# STeaMi-FP4-Alimentation.net
KiCad netlist of a schematic drawn in Altium Designer
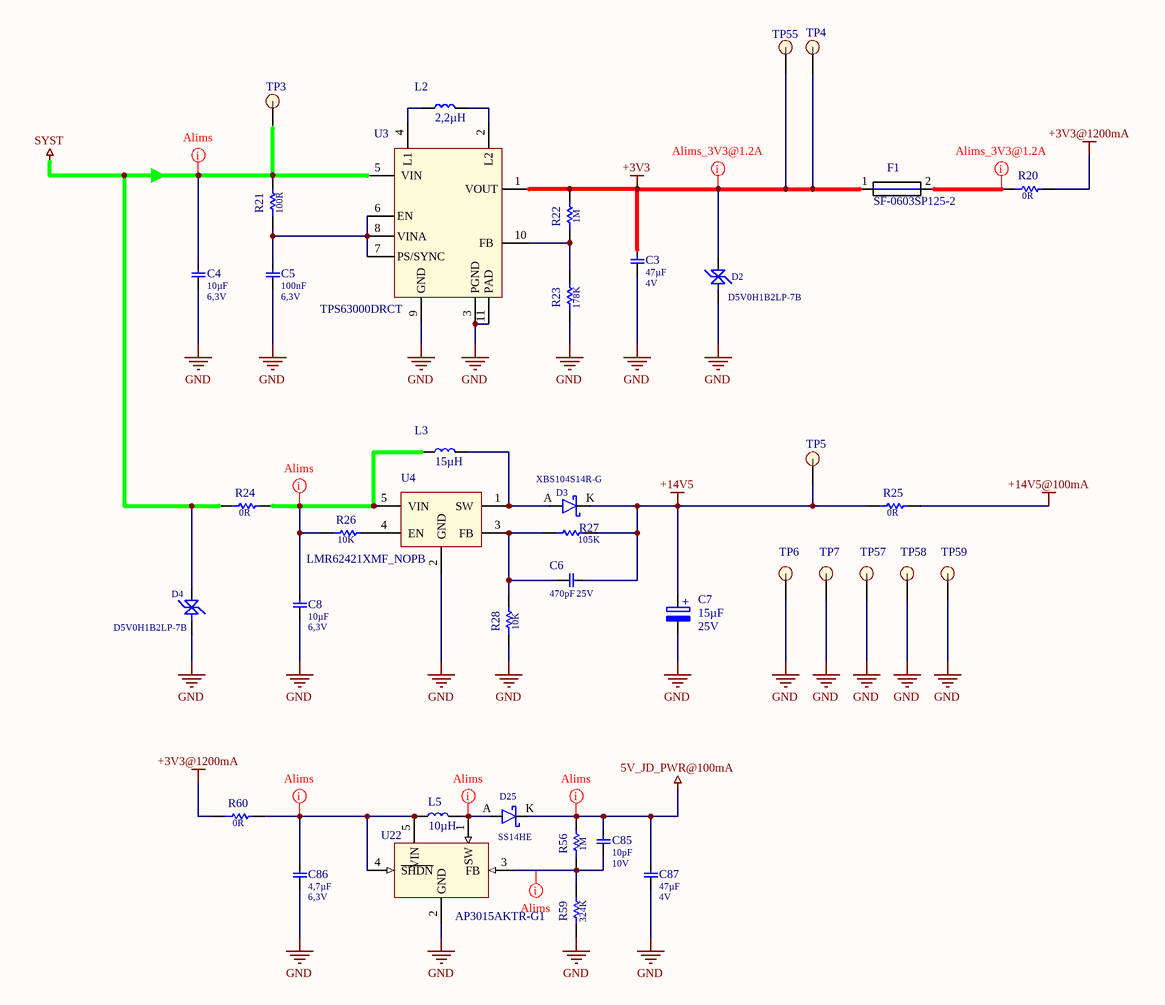
[diagram p0: STeaMi-FP4-Alimentation.SchDoc]

(export (version "E")
  (design (tool "Eeschema 10.0.6"))
  (components
    (comp (ref "C3")
      (value "~")
      (footprint "0603-CAP")
      (description "CAP CER 47µF 4V X5R 0603")
      (fields
        (field (name "MANUFACTURER") "Taiyo Yuden")
        (field (name "MANUFACTURER PART NUMBER") "AMK107BBJ476MA-RE")
        (field (name "CAPACITANCE") "47µF")
        (field (name "VOLTAGE") "4V")
        (field (name "CREATED BY") "EAG")
        (field (name "CHECKED BY") "*")
      )
      (libsource (lib "ComponentDB") (part "CAP_SYMBOL"))
    )
    (comp (ref "C4")
      (value "~")
      (footprint "0402-CAP")
      (description "CAP CER 10µF 6,3V X5R 0402")
      (fields
        (field (name "MANUFACTURER") "Murata")
        (field (name "MANUFACTURER PART NUMBER") "GRM155R60J106ME15D")
        (field (name "CAPACITANCE") "10µF")
        (field (name "VOLTAGE") "6,3V")
        (field (name "CREATED BY") "EAG")
        (field (name "CHECKED BY") "*")
      )
      (libsource (lib "ComponentDB") (part "CAP_SYMBOL"))
    )
    (comp (ref "C5")
      (value "~")
      (footprint "0402-CAP")
      (description "CAP CER 100nF 6,3V X5R 0402")
      (fields
        (field (name "MANUFACTURER") "Kyocera AVX")
        (field (name "MANUFACTURER PART NUMBER") "0402YD104KAT2A")
        (field (name "CAPACITANCE") "100nF")
        (field (name "VOLTAGE") "6,3V")
        (field (name "CREATED BY") "EAG")
        (field (name "CHECKED BY") "*")
      )
      (libsource (lib "ComponentDB") (part "CAP_SYMBOL"))
    )
    (comp (ref "C6")
      (value "~")
      (footprint "0402-CAP")
      (description "CAP CER 470pF 25V X7R 0402")
      (fields
        (field (name "MANUFACTURER") "Yageo")
        (field (name "MANUFACTURER PART NUMBER") "AC0402KRX7R8BB471")
        (field (name "CAPACITANCE") "470pF")
        (field (name "VOLTAGE") "25V")
        (field (name "CREATED BY") "EAG")
        (field (name "CHECKED BY") "*")
      )
      (libsource (lib "ComponentDB") (part "CAP_SYMBOL"))
    )
    (comp (ref "C7")
      (value "~")
      (footprint "CAPC3225X55N_1210 - TANTAL")
      (description "CAP CER 15µF 25V TANT 1210")
      (fields
        (field (name "MANUFACTURER") "Panasonic")
        (field (name "MANUFACTURER PART NUMBER") "25TQC15MYFB")
        (field (name "CAPACITANCE") "15µF")
        (field (name "VOLTAGE") "25V")
        (field (name "CREATED BY") "EAG")
      )
      (libsource (lib "ComponentDB") (part "CAP_POL_SYMBOL"))
    )
    (comp (ref "C8")
      (value "~")
      (footprint "0402-CAP")
      (description "CAP CER 10µF 6,3V X5R 0402")
      (fields
        (field (name "MANUFACTURER") "Murata")
        (field (name "MANUFACTURER PART NUMBER") "GRM155R60J106ME15D")
        (field (name "CAPACITANCE") "10µF")
        (field (name "VOLTAGE") "6,3V")
        (field (name "CREATED BY") "EAG")
        (field (name "CHECKED BY") "*")
      )
      (libsource (lib "ComponentDB") (part "CAP_SYMBOL"))
    )
    (comp (ref "C85")
      (value "~")
      (footprint "0402-CAP")
      (description "CAP CER 10pF 10V COG 0402 5%")
      (fields
        (field (name "MANUFACTURER") "WURTH Electronics")
        (field (name "MANUFACTURER PART NUMBER") "885012005007")
        (field (name "CAPACITANCE") "10pF")
        (field (name "VOLTAGE") "10V")
        (field (name "CREATED BY") "EAG")
        (field (name "CHECKED BY") "*")
      )
      (libsource (lib "ComponentDB") (part "CAP_SYMBOL"))
    )
    (comp (ref "C86")
      (value "~")
      (footprint "0402-CAP")
      (description "CAP CER 4,7µF 6,3V X5R 0402")
      (fields
        (field (name "CAPACITANCE") "4,7µF")
        (field (name "VOLTAGE") "6,3V")
        (field (name "PART NUMBER") "4,7µF-20%-6,3V-X5R-0402")
        (field (name "CREATED BY") "EAG")
        (field (name "CHECKED BY") "*")
      )
      (libsource (lib "ComponentDB") (part "CAP_SYMBOL"))
    )
    (comp (ref "C87")
      (value "~")
      (footprint "0603-CAP")
      (description "CAP CER 47µF 4V X5R 0603")
      (fields
        (field (name "CAPACITANCE") "47µF")
        (field (name "VOLTAGE") "4V")
        (field (name "PART NUMBER") "47µF-20%-4V-X5R-0603")
        (field (name "CREATED BY") "EAG")
        (field (name "CHECKED BY") "*")
      )
      (libsource (lib "ComponentDB") (part "CAP_SYMBOL"))
    )
    (comp (ref "D2")
      (value "~")
      (footprint "DFN100X60X45-2N")
      (description "ESD Suppressors / TVS Diodes Transient Voltage Suppressor PP")
      (fields
        (field (name "MANUFACTURER") "Diodes Incorporated")
        (field (name "MANUFACTURER PART NUMBER") "D5V0H1B2LP-7B")
        (field (name "PART NUMBER") "D5V0H1B2LP-7B")
        (field (name "CREATED BY") "EAG")
      )
      (libsource (lib "ComponentDB") (part "SUPPRESSORS_DIODE"))
    )
    (comp (ref "D3")
      (value "~")
      (footprint "SODFL3516X120N")
      (description "Diode Schottky 40 V 1A Montage en surface SOD-123")
      (fields
        (field (name "MANUFACTURER") "Torex Semiconductor")
        (field (name "MANUFACTURER PART NUMBER") "XBS104S14R-G")
        (field (name "PART NUMBER") "XBS104S14R-G")
        (field (name "CREATED BY") "EAG")
      )
      (libsource (lib "ComponentDB") (part "DIODE_SCHOTTKY"))
    )
    (comp (ref "D4")
      (value "~")
      (footprint "DFN100X60X45-2N")
      (description "ESD Suppressors / TVS Diodes Transient Voltage Suppressor PP")
      (fields
        (field (name "MANUFACTURER") "Diodes Incorporated")
        (field (name "MANUFACTURER PART NUMBER") "D5V0H1B2LP-7B")
        (field (name "PART NUMBER") "D5V0H1B2LP-7B")
        (field (name "CREATED BY") "EAG")
      )
      (libsource (lib "ComponentDB") (part "SUPPRESSORS_DIODE"))
    )
    (comp (ref "D25")
      (value "~")
      (footprint "SOD2314X75N-SOD323HE")
      (description "Diode Schottky 40 V 1A Montage en surface SDO-323HE")
      (fields
        (field (name "MANUFACTURER") "OnSemiconductor")
        (field (name "MANUFACTURER PART NUMBER") "SS14HE")
        (field (name "PART NUMBER") "SS14HE")
        (field (name "CREATED BY") "EAG")
      )
      (libsource (lib "ComponentDB") (part "DIODE_SCHOTTKY"))
    )
    (comp (ref "F1")
      (value "~")
      (footprint "FUSM16081X45")
      (description "Fusible 50V 1,25 A Slow blow")
      (fields
        (field (name "PART NUMBER") "SF-0603SP125-2")
        (field (name "CREATED BY") "*")
        (field (name "CHECKED BY") "*")
      )
      (libsource (lib "ComponentDB") (part "FUSE_SYMBOL"))
    )
    (comp (ref "L2")
      (value "~")
      (footprint "VLS3012")
      (description "Fixed Inductor 10µH ± 20% 1,4A 3x3x1,2mm")
      (fields
        (field (name "MANUFACTURER") "TDK")
        (field (name "MANUFACTURER PART NUMBER") "VLS3012CX-2R2M-1")
        (field (name "INDUCTANCE") "2,2µH")
        (field (name "CREATED BY") "EAG")
      )
      (libsource (lib "ComponentDB") (part "BOB_SYMBOL"))
    )
    (comp (ref "L3")
      (value "~")
      (footprint "WE-LQS_4025")
      (description "Fixed Inductor 10µH ± 20% 1,4A 5,8mm")
      (fields
        (field (name "MANUFACTURER") "Wurth")
        (field (name "MANUFACTURER PART NUMBER") "74404043150A")
        (field (name "INDUCTANCE") "15µH")
        (field (name "CREATED BY") "EAG")
      )
      (libsource (lib "ComponentDB") (part "BOB_SYMBOL"))
    )
    (comp (ref "L5")
      (value "~")
      (footprint "VLS3012")
      (description "Fixed Inductor 10µH ± 20% 1,12A 3x3x1,2mm")
      (fields
        (field (name "MANUFACTURER") "TDK")
        (field (name "MANUFACTURER PART NUMBER") "VLS3012CX-100M-1")
        (field (name "INDUCTANCE") "10µH")
        (field (name "CREATED BY") "EAG")
      )
      (libsource (lib "ComponentDB") (part "BOB_SYMBOL"))
    )
    (comp (ref "R20")
      (value "~")
      (footprint "RESC1005X40N_0402")
      (description "RES CMS 0R5%-0,0625W-0402")
      (fields
        (field (name "MANUFACTURER") "Yageo")
        (field (name "MANUFACTURER PART NUMBER") "RC0402JR-100RL")
        (field (name "RESISTANCE") "0R")
        (field (name "CREATED BY") "EAG")
      )
      (libsource (lib "ComponentDB") (part "RES_SYMBOL"))
    )
    (comp (ref "R21")
      (value "~")
      (footprint "RESC1005X40N_0402")
      (description "RES CMS 100R5%-0,0625W-0402 ±100ppm/°C")
      (fields
        (field (name "MANUFACTURER") "Yageo")
        (field (name "MANUFACTURER PART NUMBER") "RC0402JR-07100RL")
        (field (name "RESISTANCE") "100R")
        (field (name "CREATED BY") "EAG")
      )
      (libsource (lib "ComponentDB") (part "RES_SYMBOL"))
    )
    (comp (ref "R22")
      (value "~")
      (footprint "RESC1005X40N_0402")
      (description "RES CMS 1M1%-0,125W-0402 ±0ppm/°C")
      (fields
        (field (name "MANUFACTURER") "Yageo")
        (field (name "MANUFACTURER PART NUMBER") "RC0402FR-7W1ML")
        (field (name "RESISTANCE") "1M")
        (field (name "CREATED BY") "EAG")
      )
      (libsource (lib "ComponentDB") (part "RES_SYMBOL"))
    )
    (comp (ref "R23")
      (value "~")
      (footprint "RESC1005X40N_0402")
      (description "RES CMS 178K1%-0,1W-0402 ±25ppm/°C")
      (fields
        (field (name "MANUFACTURER") "Panasonic")
        (field (name "MANUFACTURER PART NUMBER") "ERJ-2RKF1783X")
        (field (name "RESISTANCE") "178K")
        (field (name "CREATED BY") "EAG")
      )
      (libsource (lib "ComponentDB") (part "RES_SYMBOL"))
    )
    (comp (ref "R24")
      (value "~")
      (footprint "RESC1005X40N_0402")
      (description "RES CMS 0R5%-0,0625W-0402")
      (fields
        (field (name "MANUFACTURER") "Yageo")
        (field (name "MANUFACTURER PART NUMBER") "RC0402JR-100RL")
        (field (name "RESISTANCE") "0R")
        (field (name "CREATED BY") "EAG")
      )
      (libsource (lib "ComponentDB") (part "RES_SYMBOL"))
    )
    (comp (ref "R25")
      (value "~")
      (footprint "RESC1005X40N_0402")
      (description "RES CMS 0R5%-0,0625W-0402")
      (fields
        (field (name "MANUFACTURER") "Yageo")
        (field (name "MANUFACTURER PART NUMBER") "RC0402JR-100RL")
        (field (name "RESISTANCE") "0R")
        (field (name "CREATED BY") "EAG")
      )
      (libsource (lib "ComponentDB") (part "RES_SYMBOL"))
    )
    (comp (ref "R26")
      (value "~")
      (footprint "RESC1005X40N_0402")
      (description "RES CMS 10K1%-0,0625W-0402 ±100ppm/°C")
      (fields
        (field (name "MANUFACTURER") "Yageo")
        (field (name "MANUFACTURER PART NUMBER") "AC0402FR-1310KL")
        (field (name "RESISTANCE") "10K")
        (field (name "CREATED BY") "EAG")
      )
      (libsource (lib "ComponentDB") (part "RES_SYMBOL"))
    )
    (comp (ref "R27")
      (value "~")
      (footprint "RESC1005X40N_0402")
      (description "RES CMS 105K0,5%-0,1W-0402 ±0ppm/°C")
      (fields
        (field (name "MANUFACTURER") "Panasonic")
        (field (name "MANUFACTURER PART NUMBER") "ERJ-2RKF1053X")
        (field (name "RESISTANCE") "105K")
        (field (name "CREATED BY") "EAG")
      )
      (libsource (lib "ComponentDB") (part "RES_SYMBOL"))
    )
    (comp (ref "R28")
      (value "~")
      (footprint "RESC1005X40N_0402")
      (description "RES CMS 10K1%-0,0625W-0402 ±100ppm/°C")
      (fields
        (field (name "MANUFACTURER") "Yageo")
        (field (name "MANUFACTURER PART NUMBER") "AC0402FR-1310KL")
        (field (name "RESISTANCE") "10K")
        (field (name "CREATED BY") "EAG")
      )
      (libsource (lib "ComponentDB") (part "RES_SYMBOL"))
    )
    (comp (ref "R56")
      (value "~")
      (footprint "RESC1005X40N_0402")
      (description "RES CMS 1M1%-0,125W-0402 ±0ppm/°C")
      (fields
        (field (name "MANUFACTURER") "Yageo")
        (field (name "MANUFACTURER PART NUMBER") "RC0402FR-7W1ML")
        (field (name "RESISTANCE") "1M")
        (field (name "CREATED BY") "EAG")
      )
      (libsource (lib "ComponentDB") (part "RES_SYMBOL"))
    )
    (comp (ref "R59")
      (value "~")
      (footprint "RESC1005X40N_0402")
      (description "RES CMS 324K1%-0,0625W-0402 ±100ppm/°C")
      (fields
        (field (name "MANUFACTURER") "Yageo")
        (field (name "MANUFACTURER PART NUMBER") "AC0402FR-07324KL")
        (field (name "RESISTANCE") "324K")
        (field (name "CREATED BY") "EAG")
      )
      (libsource (lib "ComponentDB") (part "RES_SYMBOL"))
    )
    (comp (ref "R60")
      (value "~")
      (footprint "RESC1005X40N_0402")
      (description "RES CMS 0R5%-0,0625W-0402")
      (fields
        (field (name "MANUFACTURER") "Yageo")
        (field (name "MANUFACTURER PART NUMBER") "RC0402JR-100RL")
        (field (name "RESISTANCE") "0R")
        (field (name "CREATED BY") "EAG")
      )
      (libsource (lib "ComponentDB") (part "RES_SYMBOL"))
    )
    (comp (ref "TP3")
      (value "PAD")
      (footprint "Testpoint 1mm")
      (description "TESTPOINTPAD")
      (fields
        (field (name "MANUFACTURER") "Smartembed")
        (field (name "MANUFACTURER PART NUMBER") "TESTPOINT")
        (field (name "CREATED BY") "EAG")
      )
      (libsource (lib "ComponentDB") (part "TESTPOINT"))
    )
    (comp (ref "TP4")
      (value "PAD")
      (footprint "Testpoint 1mm")
      (description "TESTPOINTPAD")
      (fields
        (field (name "MANUFACTURER") "Smartembed")
        (field (name "MANUFACTURER PART NUMBER") "TESTPOINT")
        (field (name "CREATED BY") "EAG")
      )
      (libsource (lib "ComponentDB") (part "TESTPOINT"))
    )
    (comp (ref "TP5")
      (value "PAD")
      (footprint "Testpoint 1mm")
      (description "TESTPOINTPAD")
      (fields
        (field (name "MANUFACTURER") "Smartembed")
        (field (name "MANUFACTURER PART NUMBER") "TESTPOINT")
        (field (name "CREATED BY") "EAG")
      )
      (libsource (lib "ComponentDB") (part "TESTPOINT"))
    )
    (comp (ref "TP6")
      (value "PAD")
      (footprint "Testpoint 1mm")
      (description "TESTPOINTPAD")
      (fields
        (field (name "MANUFACTURER") "Smartembed")
        (field (name "MANUFACTURER PART NUMBER") "TESTPOINT")
        (field (name "CREATED BY") "EAG")
      )
      (libsource (lib "ComponentDB") (part "TESTPOINT"))
    )
    (comp (ref "TP7")
      (value "PAD")
      (footprint "Testpoint 1mm")
      (description "TESTPOINTPAD")
      (fields
        (field (name "MANUFACTURER") "Smartembed")
        (field (name "MANUFACTURER PART NUMBER") "TESTPOINT")
        (field (name "CREATED BY") "EAG")
      )
      (libsource (lib "ComponentDB") (part "TESTPOINT"))
    )
    (comp (ref "TP55")
      (value "PAD")
      (footprint "Testpoint 1mm")
      (description "TESTPOINTPAD")
      (fields
        (field (name "MANUFACTURER") "Smartembed")
        (field (name "MANUFACTURER PART NUMBER") "TESTPOINT")
        (field (name "CREATED BY") "EAG")
      )
      (libsource (lib "ComponentDB") (part "TESTPOINT"))
    )
    (comp (ref "TP57")
      (value "PAD")
      (footprint "Testpoint 1mm")
      (description "TESTPOINTPAD")
      (fields
        (field (name "MANUFACTURER") "Smartembed")
        (field (name "MANUFACTURER PART NUMBER") "TESTPOINT")
        (field (name "CREATED BY") "EAG")
      )
      (libsource (lib "ComponentDB") (part "TESTPOINT"))
    )
    (comp (ref "TP58")
      (value "PAD")
      (footprint "Testpoint 1mm")
      (description "TESTPOINTPAD")
      (fields
        (field (name "MANUFACTURER") "Smartembed")
        (field (name "MANUFACTURER PART NUMBER") "TESTPOINT")
        (field (name "CREATED BY") "EAG")
      )
      (libsource (lib "ComponentDB") (part "TESTPOINT"))
    )
    (comp (ref "TP59")
      (value "PAD")
      (footprint "Testpoint 1mm")
      (description "TESTPOINTPAD")
      (fields
        (field (name "MANUFACTURER") "Smartembed")
        (field (name "MANUFACTURER PART NUMBER") "TESTPOINT")
        (field (name "CREATED BY") "EAG")
      )
      (libsource (lib "ComponentDB") (part "TESTPOINT"))
    )
    (comp (ref "U3")
      (value "~")
      (footprint "VSON-10")
      (description "High Efficient single inductor buck-boost converter with 1,8-A switches ajustable")
      (fields
        (field (name "MANUFACTURER") "Texas Instruments")
        (field (name "MANUFACTURER PART NUMBER") "TPS63000DRCT")
        (field (name "PART NUMBER") "TPS63000")
        (field (name "CREATED BY") "EAG")
        (field (name "CHECKED BY") "*")
      )
      (libsource (lib "ComponentDB") (part "TPS63000"))
    )
    (comp (ref "U4")
      (value "~")
      (footprint "SOT95P270X145-5N")
      (description "Simple Switcher 24Vout 2,1A Step-Up SOT-23")
      (fields
        (field (name "MANUFACTURER") "Texas Instruments")
        (field (name "MANUFACTURER PART NUMBER") "LMR62421XMF_NOPB")
        (field (name "PART NUMBER") "LMR62421XMF_NOPB")
        (field (name "CREATED BY") "EAG")
        (field (name "CHECKED BY") "*")
      )
      (libsource (lib "ComponentDB") (part "LMR62421XMF_NOPB"))
    )
    (comp (ref "U22")
      (value "~")
      (footprint "SOT95P280X100-5N SOT23-5")
      (fields
        (field (name "MANUFACTURER") "Diodes Incorporated")
        (field (name "MANUFACTURER PART NUMBER") "AP3015AKTR-G1")
        (field (name "PART NUMBER") "AP3015AKTR-G1")
        (field (name "CREATED BY") "EAG")
        (field (name "CHECKED BY") "*")
      )
      (libsource (lib "ComponentDB") (part "AP3015AKTR-G1"))
    )
  )
  (nets
    (net (code "1") (name "+3V3") (class "Default")
      (node (ref "C3") (pin "2") (pinfunction "2_2") (pintype "passive"))
      (node (ref "D2") (pin "1") (pinfunction "A_1") (pintype "passive"))
      (node (ref "F1") (pin "1") (pinfunction "1_1") (pintype "passive"))
      (node (ref "R22") (pin "2") (pinfunction "2_2") (pintype "passive"))
      (node (ref "TP4") (pin "1") (pinfunction "1_1") (pintype "passive"))
      (node (ref "TP55") (pin "1") (pinfunction "1_1") (pintype "passive"))
      (node (ref "U3") (pin "1") (pinfunction "VOUT_1") (pintype "passive"))
    )
    (net (code "2") (name "+3V3@1200mA") (class "Default")
      (node (ref "R20") (pin "2") (pinfunction "2_2") (pintype "passive"))
      (node (ref "R60") (pin "1") (pinfunction "1_1") (pintype "passive"))
    )
    (net (code "3") (name "+14V5") (class "Default")
      (node (ref "C6") (pin "2") (pinfunction "2_2") (pintype "passive"))
      (node (ref "C7") (pin "1") (pinfunction "1_1") (pintype "passive"))
      (node (ref "D3") (pin "K") (pinfunction "K_K") (pintype "passive"))
      (node (ref "R25") (pin "1") (pinfunction "1_1") (pintype "passive"))
      (node (ref "R27") (pin "2") (pinfunction "2_2") (pintype "passive"))
      (node (ref "TP5") (pin "1") (pinfunction "1_1") (pintype "passive"))
    )
    (net (code "4") (name "+14V5@100mA") (class "Default")
      (node (ref "R25") (pin "2") (pinfunction "2_2") (pintype "passive"))
    )
    (net (code "5") (name "5V_JD_PWR@100mA") (class "Default")
      (node (ref "C85") (pin "2") (pinfunction "2_2") (pintype "passive"))
      (node (ref "C87") (pin "2") (pinfunction "2_2") (pintype "passive"))
      (node (ref "D25") (pin "K") (pinfunction "K_K") (pintype "passive"))
      (node (ref "R56") (pin "2") (pinfunction "2_2") (pintype "passive"))
    )
    (net (code "6") (name "GND") (class "Default")
      (node (ref "C3") (pin "1") (pinfunction "1_1") (pintype "passive"))
      (node (ref "C4") (pin "1") (pinfunction "1_1") (pintype "passive"))
      (node (ref "C5") (pin "1") (pinfunction "1_1") (pintype "passive"))
      (node (ref "C7") (pin "2") (pinfunction "2_2") (pintype "passive"))
      (node (ref "C8") (pin "1") (pinfunction "1_1") (pintype "passive"))
      (node (ref "C86") (pin "1") (pinfunction "1_1") (pintype "passive"))
      (node (ref "C87") (pin "1") (pinfunction "1_1") (pintype "passive"))
      (node (ref "D2") (pin "2") (pinfunction "K_2") (pintype "passive"))
      (node (ref "D4") (pin "2") (pinfunction "K_2") (pintype "passive"))
      (node (ref "R23") (pin "1") (pinfunction "1_1") (pintype "passive"))
      (node (ref "R28") (pin "1") (pinfunction "1_1") (pintype "passive"))
      (node (ref "R59") (pin "1") (pinfunction "1_1") (pintype "passive"))
      (node (ref "TP57") (pin "1") (pinfunction "1_1") (pintype "passive"))
      (node (ref "TP58") (pin "1") (pinfunction "1_1") (pintype "passive"))
      (node (ref "TP59") (pin "1") (pinfunction "1_1") (pintype "passive"))
      (node (ref "TP6") (pin "1") (pinfunction "1_1") (pintype "passive"))
      (node (ref "TP7") (pin "1") (pinfunction "1_1") (pintype "passive"))
      (node (ref "U22") (pin "2") (pinfunction "GND_2") (pintype "power_in"))
      (node (ref "U3") (pin "11") (pinfunction "PAD_11") (pintype "passive"))
      (node (ref "U3") (pin "3") (pinfunction "PGND_3") (pintype "passive"))
      (node (ref "U3") (pin "9") (pinfunction "GND_9") (pintype "passive"))
      (node (ref "U4") (pin "2") (pinfunction "GND_2") (pintype "passive"))
    )
    (net (code "7") (name "Net-(F1-Pad2)") (class "Default")
      (node (ref "F1") (pin "2") (pinfunction "2_2") (pintype "passive"))
      (node (ref "R20") (pin "1") (pinfunction "1_1") (pintype "passive"))
    )
    (net (code "8") (name "Net-(U3-EN)") (class "Default")
      (node (ref "C5") (pin "2") (pinfunction "2_2") (pintype "passive"))
      (node (ref "R21") (pin "1") (pinfunction "1_1") (pintype "passive"))
      (node (ref "U3") (pin "6") (pinfunction "EN_6") (pintype "passive"))
      (node (ref "U3") (pin "7") (pinfunction "PS/SYNC_7") (pintype "passive"))
      (node (ref "U3") (pin "8") (pinfunction "VINA_8") (pintype "passive"))
    )
    (net (code "9") (name "Net-(U3-FB)") (class "Default")
      (node (ref "R22") (pin "1") (pinfunction "1_1") (pintype "passive"))
      (node (ref "R23") (pin "2") (pinfunction "2_2") (pintype "passive"))
      (node (ref "U3") (pin "10") (pinfunction "FB_10") (pintype "passive"))
    )
    (net (code "10") (name "Net-(U3-L1)") (class "Default")
      (node (ref "L2") (pin "1") (pinfunction "1_1") (pintype "passive"))
      (node (ref "U3") (pin "4") (pinfunction "L1_4") (pintype "passive"))
    )
    (net (code "11") (name "Net-(U3-L2)") (class "Default")
      (node (ref "L2") (pin "2") (pinfunction "2_2") (pintype "passive"))
      (node (ref "U3") (pin "2") (pinfunction "L2_2") (pintype "passive"))
    )
    (net (code "12") (name "Net-(U4-EN)") (class "Default")
      (node (ref "R26") (pin "2") (pinfunction "2_2") (pintype "passive"))
      (node (ref "U4") (pin "4") (pinfunction "EN_4") (pintype "passive"))
    )
    (net (code "13") (name "Net-(U4-FB)") (class "Default")
      (node (ref "C6") (pin "1") (pinfunction "1_1") (pintype "passive"))
      (node (ref "R27") (pin "1") (pinfunction "1_1") (pintype "passive"))
      (node (ref "R28") (pin "2") (pinfunction "2_2") (pintype "passive"))
      (node (ref "U4") (pin "3") (pinfunction "FB_3") (pintype "passive"))
    )
    (net (code "14") (name "Net-(U4-SW)") (class "Default")
      (node (ref "D3") (pin "A") (pinfunction "A_A") (pintype "passive"))
      (node (ref "L3") (pin "2") (pinfunction "2_2") (pintype "passive"))
      (node (ref "U4") (pin "1") (pinfunction "SW_1") (pintype "passive"))
    )
    (net (code "15") (name "Net-(U4-VIN)") (class "Default")
      (node (ref "C8") (pin "2") (pinfunction "2_2") (pintype "passive"))
      (node (ref "L3") (pin "1") (pinfunction "1_1") (pintype "passive"))
      (node (ref "R24") (pin "2") (pinfunction "2_2") (pintype "passive"))
      (node (ref "R26") (pin "1") (pinfunction "1_1") (pintype "passive"))
      (node (ref "U4") (pin "5") (pinfunction "VIN_5") (pintype "passive"))
    )
    (net (code "16") (name "Net-(U22-FB)") (class "Default")
      (node (ref "C85") (pin "1") (pinfunction "1_1") (pintype "passive"))
      (node (ref "R56") (pin "1") (pinfunction "1_1") (pintype "passive"))
      (node (ref "R59") (pin "2") (pinfunction "2_2") (pintype "passive"))
      (node (ref "U22") (pin "3") (pinfunction "FB_3") (pintype "input"))
    )
    (net (code "17") (name "Net-(U22-SW)") (class "Default")
      (node (ref "D25") (pin "A") (pinfunction "A_A") (pintype "passive"))
      (node (ref "L5") (pin "2") (pinfunction "2_2") (pintype "passive"))
      (node (ref "U22") (pin "1") (pinfunction "SW_1") (pintype "input"))
    )
    (net (code "18") (name "Net-(U22-VIN)") (class "Default")
      (node (ref "C86") (pin "2") (pinfunction "2_2") (pintype "passive"))
      (node (ref "L5") (pin "1") (pinfunction "1_1") (pintype "passive"))
      (node (ref "R60") (pin "2") (pinfunction "2_2") (pintype "passive"))
      (node (ref "U22") (pin "4") (pinfunction "~{SHDN}_4") (pintype "input"))
      (node (ref "U22") (pin "5") (pinfunction "VIN_5") (pintype "power_in"))
    )
    (net (code "19") (name "SYST") (class "Default")
      (node (ref "C4") (pin "2") (pinfunction "2_2") (pintype "passive"))
      (node (ref "D4") (pin "1") (pinfunction "A_1") (pintype "passive"))
      (node (ref "R21") (pin "2") (pinfunction "2_2") (pintype "passive"))
      (node (ref "R24") (pin "1") (pinfunction "1_1") (pintype "passive"))
      (node (ref "TP3") (pin "1") (pinfunction "1_1") (pintype "passive"))
      (node (ref "U3") (pin "5") (pinfunction "VIN_5") (pintype "passive"))
    )
  )
)
